# regulator_2025-05-19.net
KiCad netlist of a schematic drawn in Altium Designer
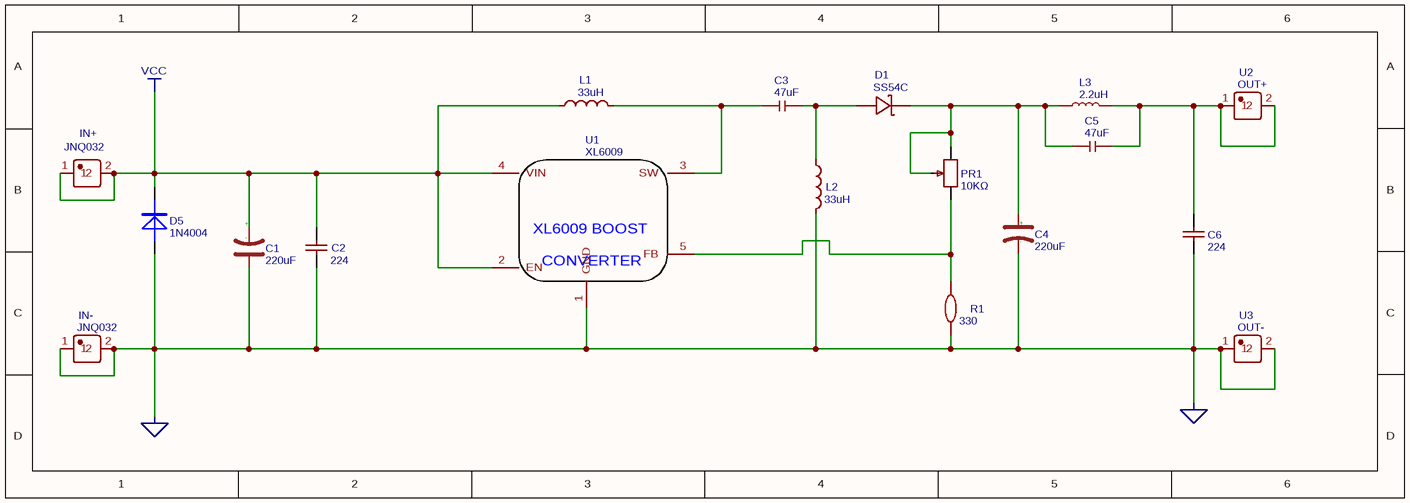
[diagram p0: regulator_2025-05-19.schdoc]

(export (version "E")
  (design (tool "Eeschema 10.0.6"))
  (components
    (comp (ref "C1")
      (value "220uF")
      (footprint "ELECTRO-SMD-C-6MM")
      (fields (field (name "MANUFACTURER PART") "CS1E221M-CRE77"))
      (libsource (lib "altium-import") (part "root_1_220uF_"))
    )
    (comp (ref "C2")
      (value "224")
      (footprint "C0805")
      (fields (field (name "MANUFACTURER") "FH") (field (name "MANUFACTURER PART") "0805F224M500NT"))
      (libsource (lib "altium-import") (part "root_1_224_"))
    )
    (comp (ref "C3")
      (value "47uF")
      (footprint "C1210")
      (fields (field (name "MANUFACTURER PART") "GRM32ER71A476ME15L"))
      (libsource (lib "altium-import") (part "root_0_47uF_"))
    )
    (comp (ref "C4")
      (value "220uF")
      (footprint "ELECTRO-SMD-C-6MM")
      (fields (field (name "MANUFACTURER PART") "CS1E221M-CRE77"))
      (libsource (lib "altium-import") (part "root_3_220uF_"))
    )
    (comp (ref "C5")
      (value "47uF")
      (footprint "C1210")
      (fields (field (name "MANUFACTURER PART") "GRM32ER71A476ME15L"))
      (libsource (lib "altium-import") (part "root_0_47uF_"))
    )
    (comp (ref "C6")
      (value "224")
      (footprint "C0805")
      (fields (field (name "MANUFACTURER") "FH") (field (name "MANUFACTURER PART") "0805F224M500NT"))
      (libsource (lib "altium-import") (part "root_1_224_"))
    )
    (comp (ref "D1")
      (value "SS54C")
      (footprint "SMC_L7.5-W5.8-LS8.3-RD")
      (fields
        (field (name "MANUFACTURER") "LGE(鲁光)")
        (field (name "MANUFACTURER PART") "SS54")
        (field (name "CONTRIBUTOR") "LCSC")
      )
      (libsource (lib "altium-import") (part "root_2_SS54C_"))
    )
    (comp (ref "D5")
      (value "1N4004")
      (footprint "SMA-DO214AC")
      (fields (field (name "MANUFACTURER PART") "?"))
      (libsource (lib "altium-import") (part "root_3_1N4004_"))
    )
    (comp (ref "IN+")
      (value "JNQ032")
      (footprint "CONN-TH_JNQ032")
      (fields (field (name "MANUFACTURER") "TML(特米勒)") (field (name "CONTRIBUTOR") "LCSC"))
      (libsource (lib "altium-import") (part "root_0_JNQ032_"))
    )
    (comp (ref "IN-")
      (value "JNQ032")
      (footprint "CONN-TH_JNQ032")
      (fields (field (name "MANUFACTURER") "TML(特米勒)") (field (name "CONTRIBUTOR") "LCSC"))
      (libsource (lib "altium-import") (part "root_0_JNQ032_"))
    )
    (comp (ref "L1")
      (value "33uH")
      (footprint "IND-SMD_L12.3-W12.3")
      (fields
        (field (name "MANUFACTURER") "SHOU HAN(首韩)")
        (field (name "MANUFACTURER PART") "CYH125-33UH")
        (field (name "CONTRIBUTOR") "lcsc")
      )
      (libsource (lib "altium-import") (part "root_0_33uH_"))
    )
    (comp (ref "L2")
      (value "33uH")
      (footprint "IND-SMD_L12.3-W12.3")
      (fields
        (field (name "MANUFACTURER") "SHOU HAN(首韩)")
        (field (name "MANUFACTURER PART") "CYH125-33UH")
        (field (name "CONTRIBUTOR") "lcsc")
      )
      (libsource (lib "altium-import") (part "root_3_33uH_"))
    )
    (comp (ref "L3")
      (value "2.2uH")
      (footprint "INT2-SMD-4.8X4.6X1.0MM")
      (fields (field (name "MANUFACTURER PART") "VLF5010ST-2R2M2R0"))
      (libsource (lib "altium-import") (part "root_0_2.2uH_"))
    )
    (comp (ref "PR1")
      (value "10KΩ")
      (footprint "RES-ADJ_3296W")
      (fields (field (name "MANUFACTURER") "ReliaPro") (field (name "MANUFACTURER PART") "3296W-1-103"))
      (libsource (lib "altium-import") (part "root_0_10KΩ_"))
    )
    (comp (ref "R1")
      (value "330")
      (footprint "R0805")
      (fields
        (field (name "MANUFACTURER") "YAGEO(国巨)")
        (field (name "MANUFACTURER PART") "AC0805JR-07330RL")
        (field (name "CONTRIBUTOR") "LCSC")
      )
      (libsource (lib "altium-import") (part "root_1_330_"))
    )
    (comp (ref "U1")
      (value "XL6009")
      (footprint "TO-263-5")
      (fields (field (name "MANUFACTURER") "XLSEMI") (field (name "CONTRIBUTOR") "GerryChen"))
      (libsource (lib "altium-import") (part "root_0_XL6009_"))
    )
    (comp (ref "U2")
      (value "OUT+")
      (footprint "CONN-TH_JNQ032")
      (fields
        (field (name "MANUFACTURER") "TML(特米勒)")
        (field (name "MANUFACTURER PART") "JNQ032")
        (field (name "CONTRIBUTOR") "LCSC")
      )
      (libsource (lib "altium-import") (part "root_0_OUT+_"))
    )
    (comp (ref "U3")
      (value "OUT-")
      (footprint "CONN-TH_JNQ032")
      (fields
        (field (name "MANUFACTURER") "TML(特米勒)")
        (field (name "MANUFACTURER PART") "JNQ032")
        (field (name "CONTRIBUTOR") "LCSC")
      )
      (libsource (lib "altium-import") (part "root_0_OUT-_"))
    )
  )
  (nets
    (net (code "1") (name "GND") (class "Default")
      (node (ref "C1") (pin "+") (pinfunction "+_+") (pintype "passive"))
      (node (ref "C2") (pin "1") (pinfunction "1_1") (pintype "passive"))
      (node (ref "C4") (pin "-") (pinfunction "-_-") (pintype "passive"))
      (node (ref "C6") (pin "1") (pinfunction "1_1") (pintype "passive"))
      (node (ref "D5") (pin "A") (pinfunction "A_A") (pintype "passive"))
      (node (ref "IN-") (pin "1") (pinfunction "1_1") (pintype "passive"))
      (node (ref "IN-") (pin "2") (pinfunction "2_2") (pintype "passive"))
      (node (ref "L2") (pin "2") (pinfunction "2_2") (pintype "passive"))
      (node (ref "R1") (pin "1") (pinfunction "1_1") (pintype "passive"))
      (node (ref "U1") (pin "1") (pinfunction "GND_1") (pintype "passive"))
      (node (ref "U3") (pin "1") (pinfunction "1_1") (pintype "passive"))
      (node (ref "U3") (pin "2") (pinfunction "2_2") (pintype "passive"))
    )
    (net (code "2") (name "Net-(C5-Pad2)") (class "Default")
      (node (ref "C5") (pin "2") (pinfunction "2_2") (pintype "passive"))
      (node (ref "C6") (pin "2") (pinfunction "2_2") (pintype "passive"))
      (node (ref "L3") (pin "2") (pinfunction "2_2") (pintype "passive"))
      (node (ref "U2") (pin "1") (pinfunction "1_1") (pintype "passive"))
      (node (ref "U2") (pin "2") (pinfunction "2_2") (pintype "passive"))
    )
    (net (code "3") (name "Net-(D1-A)") (class "Default")
      (node (ref "C3") (pin "2") (pinfunction "2_2") (pintype "passive"))
      (node (ref "D1") (pin "2") (pinfunction "A_2") (pintype "passive"))
      (node (ref "L2") (pin "1") (pinfunction "1_1") (pintype "passive"))
    )
    (net (code "4") (name "Net-(D1-K)") (class "Default")
      (node (ref "C4") (pin "+") (pinfunction "+_+") (pintype "passive"))
      (node (ref "C5") (pin "1") (pinfunction "1_1") (pintype "passive"))
      (node (ref "D1") (pin "1") (pinfunction "K_1") (pintype "passive"))
      (node (ref "L3") (pin "1") (pinfunction "1_1") (pintype "passive"))
      (node (ref "PR1") (pin "1") (pinfunction "1_1") (pintype "passive"))
      (node (ref "PR1") (pin "2") (pinfunction "2_2") (pintype "passive"))
    )
    (net (code "5") (name "Net-(U1-FB)") (class "Default")
      (node (ref "PR1") (pin "3") (pinfunction "3_3") (pintype "passive"))
      (node (ref "R1") (pin "2") (pinfunction "2_2") (pintype "passive"))
      (node (ref "U1") (pin "5") (pinfunction "FB_5") (pintype "passive"))
    )
    (net (code "6") (name "Net-(U1-SW)") (class "Default")
      (node (ref "C3") (pin "1") (pinfunction "1_1") (pintype "passive"))
      (node (ref "L1") (pin "2") (pinfunction "2_2") (pintype "passive"))
      (node (ref "U1") (pin "3") (pinfunction "SW_3") (pintype "passive"))
    )
    (net (code "7") (name "VCC") (class "Default")
      (node (ref "C1") (pin "-") (pinfunction "-_-") (pintype "passive"))
      (node (ref "C2") (pin "2") (pinfunction "2_2") (pintype "passive"))
      (node (ref "D5") (pin "K") (pinfunction "K_K") (pintype "passive"))
      (node (ref "IN+") (pin "1") (pinfunction "1_1") (pintype "passive"))
      (node (ref "IN+") (pin "2") (pinfunction "2_2") (pintype "passive"))
      (node (ref "L1") (pin "1") (pinfunction "1_1") (pintype "passive"))
      (node (ref "U1") (pin "2") (pinfunction "EN_2") (pintype "passive"))
      (node (ref "U1") (pin "4") (pinfunction "VIN_4") (pintype "passive"))
    )
  )
)
